# SAM70.net
KiCad netlist of a schematic drawn in Altium Designer
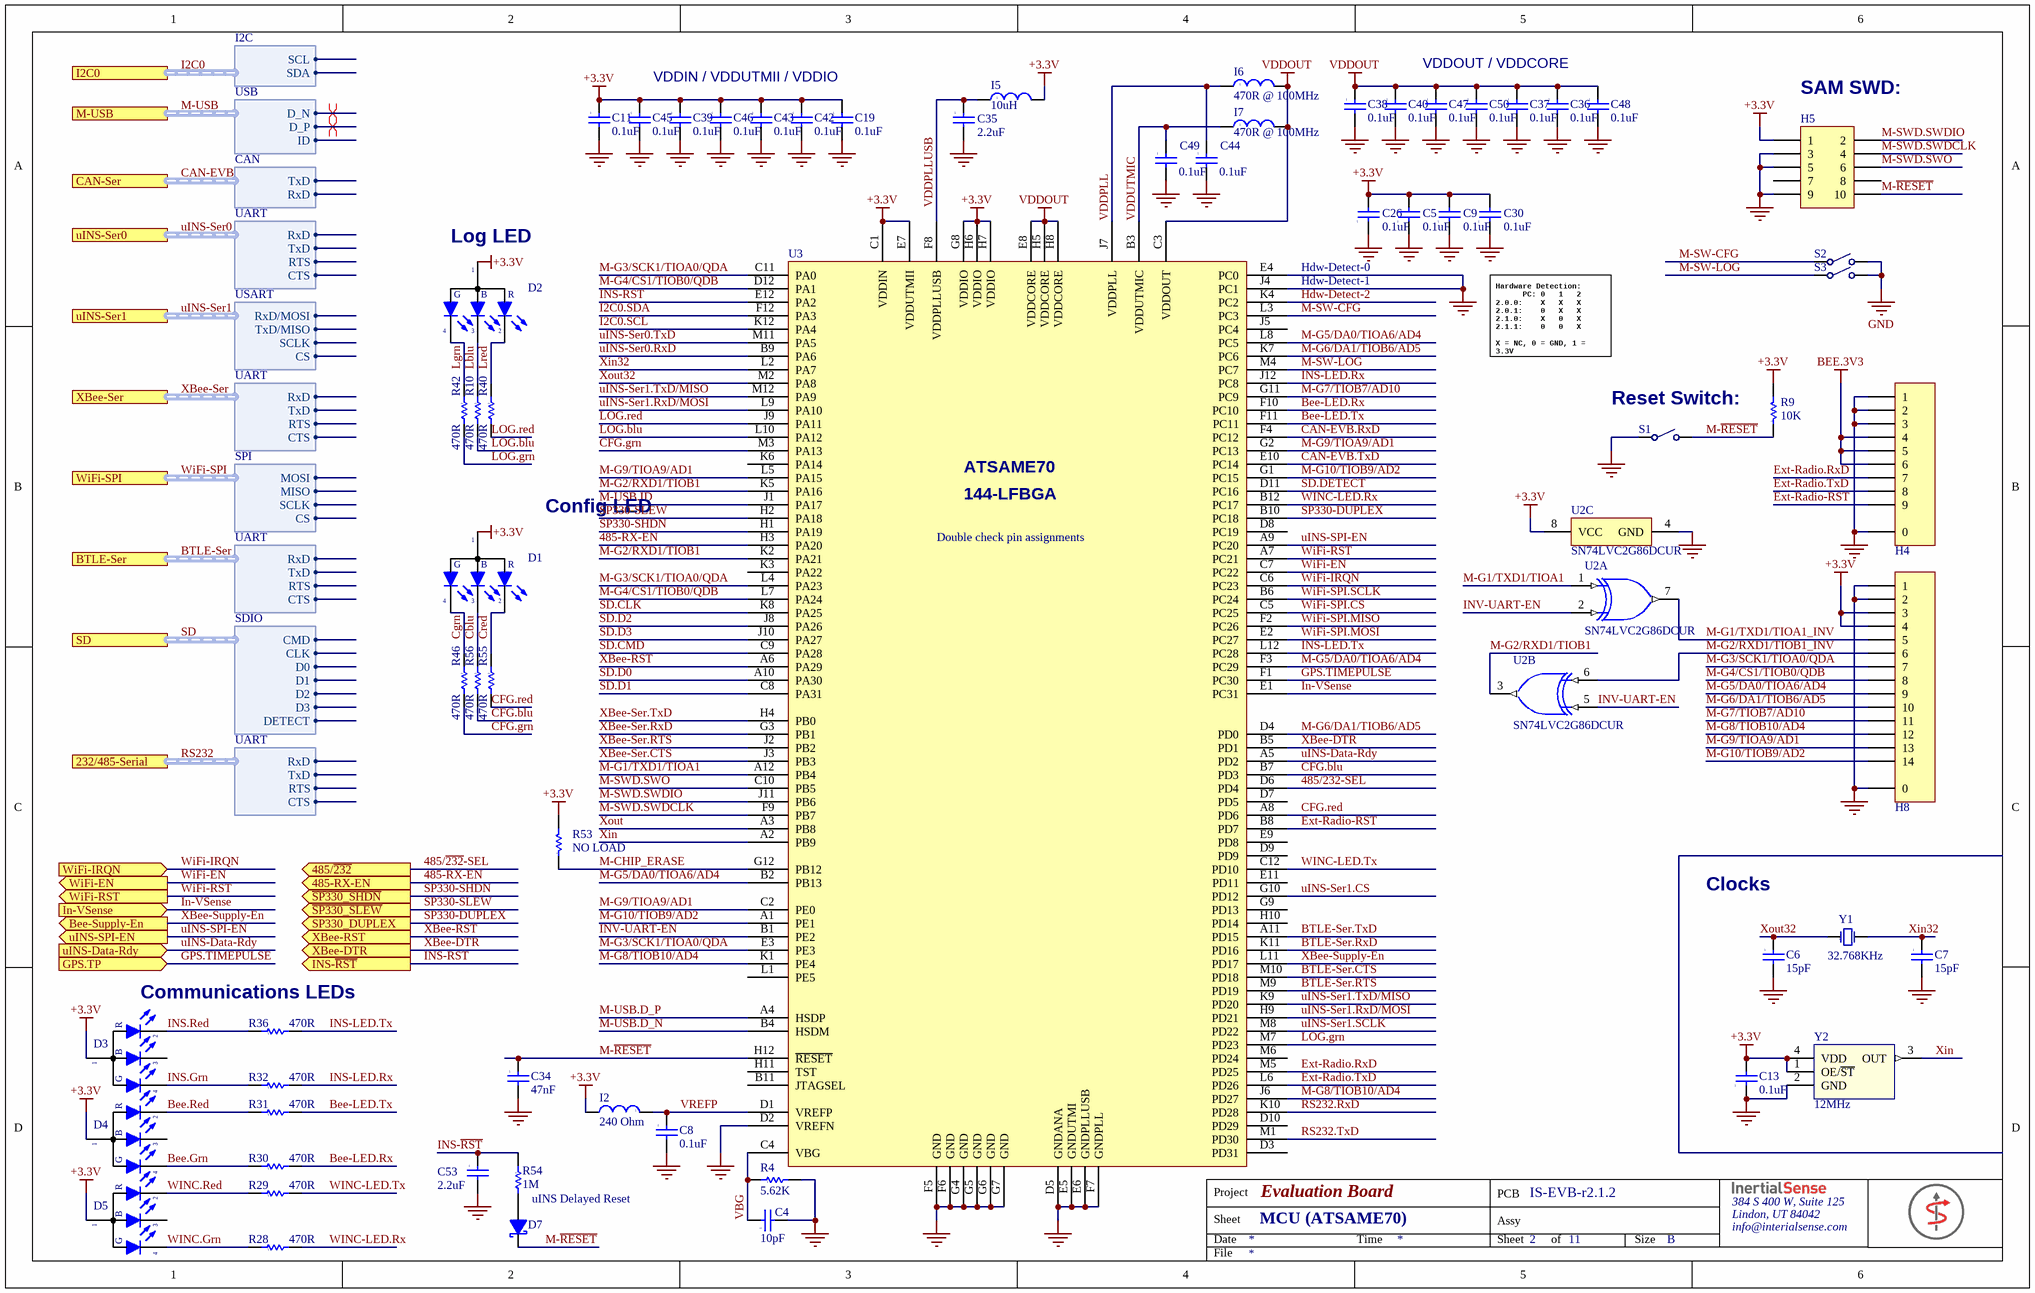
[diagram p0: SAM70.SchDoc]

(export (version "E")
  (design (tool "Eeschema 10.0.6"))
  (components
    (comp (ref "C4")
      (value "10pF")
      (footprint "0402")
      (description "CAP CER 10PF 50V C0G 0402")
      (fields
        (field (name "MANUFACTURER") "TDK")
        (field (name "MANUFACTURER PART NUMBER") "C1005C0G1H100D050BA")
        (field (name "PUBLISHER") "Altium Limited")
      )
      (libsource (lib "General") (part "Cap"))
    )
    (comp (ref "C5")
      (value "0.1uF")
      (footprint "0402")
      (description "CAP CER .10UF 50V X7R 10% 0402")
      (fields
        (field (name "MANUFACTURER") "TDK Corporation")
        (field (name "MANUFACTURER PART NUMBER") "C1005X7R1H104K")
        (field (name "PUBLISHER") "Altium Limited")
      )
      (libsource (lib "") (part "Cap_1"))
    )
    (comp (ref "C6")
      (value "15pF")
      (footprint "0402")
      (description "CAP CER 15PF 16V C0G/NP0 0402")
      (fields
        (field (name "MANUFACTURER") "KEMET")
        (field (name "MANUFACTURER PART NUMBER") "C0402C150J4GACTU")
        (field (name "PUBLISHER") "Altium Limited")
      )
      (libsource (lib "General") (part "Cap"))
    )
    (comp (ref "C7")
      (value "15pF")
      (footprint "0402")
      (description "CAP CER 15PF 16V C0G/NP0 0402")
      (fields
        (field (name "MANUFACTURER") "KEMET")
        (field (name "MANUFACTURER PART NUMBER") "C0402C150J4GACTU")
        (field (name "PUBLISHER") "Altium Limited")
      )
      (libsource (lib "General") (part "Cap"))
    )
    (comp (ref "C8")
      (value "0.1uF")
      (footprint "0201")
      (description "CAP CER 0.1UF 25V X5R 0201")
      (fields
        (field (name "MANUFACTURER") "Murata")
        (field (name "MANUFACTURER PART NUMBER") "GRM033R6YA104KE14D")
        (field (name "PUBLISHER") "Altium Limited")
      )
      (libsource (lib "General") (part "Cap"))
    )
    (comp (ref "C9")
      (value "0.1uF")
      (footprint "0402")
      (description "CAP CER .10UF 50V X7R 10% 0402")
      (fields
        (field (name "MANUFACTURER") "TDK Corporation")
        (field (name "MANUFACTURER PART NUMBER") "C1005X7R1H104K")
        (field (name "PUBLISHER") "Altium Limited")
      )
      (libsource (lib "") (part "Cap_1"))
    )
    (comp (ref "C11")
      (value "0.1uF")
      (footprint "0201")
      (description "CAP CER 0.1UF 25V X5R 0201")
      (fields
        (field (name "MANUFACTURER") "Murata")
        (field (name "MANUFACTURER PART NUMBER") "GRM033R6YA104KE14D")
        (field (name "PUBLISHER") "Altium Limited")
      )
      (libsource (lib "General") (part "Cap"))
    )
    (comp (ref "C13")
      (value "0.1uF")
      (footprint "0402")
      (description "CAP CER .10UF 50V X7R 10% 0402")
      (fields
        (field (name "MANUFACTURER") "TDK Corporation")
        (field (name "MANUFACTURER PART NUMBER") "C1005X7R1H104K")
        (field (name "PUBLISHER") "Altium Limited")
      )
      (libsource (lib "") (part "Cap_1"))
    )
    (comp (ref "C19")
      (value "0.1uF")
      (footprint "0201")
      (description "CAP CER 0.1UF 25V X5R 0201")
      (fields
        (field (name "MANUFACTURER") "Murata")
        (field (name "MANUFACTURER PART NUMBER") "GRM033R6YA104KE14D")
        (field (name "PUBLISHER") "Altium Limited")
      )
      (libsource (lib "General") (part "Cap"))
    )
    (comp (ref "C26")
      (value "0.1uF")
      (footprint "0402")
      (description "CAP CER .10UF 50V X7R 10% 0402")
      (fields
        (field (name "MANUFACTURER") "TDK Corporation")
        (field (name "MANUFACTURER PART NUMBER") "C1005X7R1H104K")
        (field (name "PUBLISHER") "Altium Limited")
      )
      (libsource (lib "") (part "Cap_1"))
    )
    (comp (ref "C30")
      (value "0.1uF")
      (footprint "0402")
      (description "CAP CER .10UF 50V X7R 10% 0402")
      (fields
        (field (name "MANUFACTURER") "TDK Corporation")
        (field (name "MANUFACTURER PART NUMBER") "C1005X7R1H104K")
        (field (name "PUBLISHER") "Altium Limited")
      )
      (libsource (lib "") (part "Cap_1"))
    )
    (comp (ref "C34")
      (value "47nF")
      (footprint "0402")
      (description "CAP CER 0.047UF 16V Y5V 0402")
      (fields
        (field (name "MANUFACTURER") "Yageo")
        (field (name "MANUFACTURER PART NUMBER") "CC0402ZRY5V7BB473")
        (field (name "PUBLISHER") "Altium Limited")
      )
      (libsource (lib "General") (part "Cap"))
    )
    (comp (ref "C35")
      (value "Cap")
      (footprint "0603")
      (description "CAP CER 2.2UF 6.3V X5R 0603")
      (fields
        (field (name "MANUFACTURER") "Samsung")
        (field (name "MANUFACTURER PART NUMBER") "CL10A225KQ8NNWC")
        (field (name "CAPACITANCE") "2.2uF")
      )
      (libsource (lib "General") (part "Cap"))
    )
    (comp (ref "C36")
      (value "0.1uF")
      (footprint "0201")
      (description "CAP CER 0.1UF 25V X5R 0201")
      (fields
        (field (name "MANUFACTURER") "Murata")
        (field (name "MANUFACTURER PART NUMBER") "GRM033R6YA104KE14D")
        (field (name "PUBLISHER") "Altium Limited")
      )
      (libsource (lib "General") (part "Cap"))
    )
    (comp (ref "C37")
      (value "0.1uF")
      (footprint "0201")
      (description "CAP CER 0.1UF 25V X5R 0201")
      (fields
        (field (name "MANUFACTURER") "Murata")
        (field (name "MANUFACTURER PART NUMBER") "GRM033R6YA104KE14D")
        (field (name "PUBLISHER") "Altium Limited")
      )
      (libsource (lib "General") (part "Cap"))
    )
    (comp (ref "C38")
      (value "0.1uF")
      (footprint "0201")
      (description "CAP CER 0.1UF 25V X5R 0201")
      (fields
        (field (name "MANUFACTURER") "Murata")
        (field (name "MANUFACTURER PART NUMBER") "GRM033R6YA104KE14D")
        (field (name "PUBLISHER") "Altium Limited")
      )
      (libsource (lib "General") (part "Cap"))
    )
    (comp (ref "C39")
      (value "0.1uF")
      (footprint "0201")
      (description "CAP CER 0.1UF 25V X5R 0201")
      (fields
        (field (name "MANUFACTURER") "Murata")
        (field (name "MANUFACTURER PART NUMBER") "GRM033R6YA104KE14D")
        (field (name "PUBLISHER") "Altium Limited")
      )
      (libsource (lib "General") (part "Cap"))
    )
    (comp (ref "C40")
      (value "0.1uF")
      (footprint "0201")
      (description "CAP CER 0.1UF 25V X5R 0201")
      (fields
        (field (name "MANUFACTURER") "Murata")
        (field (name "MANUFACTURER PART NUMBER") "GRM033R6YA104KE14D")
        (field (name "PUBLISHER") "Altium Limited")
      )
      (libsource (lib "General") (part "Cap"))
    )
    (comp (ref "C42")
      (value "0.1uF")
      (footprint "0201")
      (description "CAP CER 0.1UF 25V X5R 0201")
      (fields
        (field (name "MANUFACTURER") "Murata")
        (field (name "MANUFACTURER PART NUMBER") "GRM033R6YA104KE14D")
        (field (name "PUBLISHER") "Altium Limited")
      )
      (libsource (lib "General") (part "Cap"))
    )
    (comp (ref "C43")
      (value "0.1uF")
      (footprint "0201")
      (description "CAP CER 0.1UF 25V X5R 0201")
      (fields
        (field (name "MANUFACTURER") "Murata")
        (field (name "MANUFACTURER PART NUMBER") "GRM033R6YA104KE14D")
        (field (name "PUBLISHER") "Altium Limited")
      )
      (libsource (lib "General") (part "Cap"))
    )
    (comp (ref "C44")
      (value "0.1uF")
      (footprint "0201")
      (description "CAP CER 0.1UF 25V X5R 0201")
      (fields
        (field (name "MANUFACTURER") "Murata")
        (field (name "MANUFACTURER PART NUMBER") "GRM033R6YA104KE14D")
        (field (name "PUBLISHER") "Altium Limited")
      )
      (libsource (lib "General") (part "Cap"))
    )
    (comp (ref "C45")
      (value "0.1uF")
      (footprint "0201")
      (description "CAP CER 0.1UF 25V X5R 0201")
      (fields
        (field (name "MANUFACTURER") "Murata")
        (field (name "MANUFACTURER PART NUMBER") "GRM033R6YA104KE14D")
        (field (name "PUBLISHER") "Altium Limited")
      )
      (libsource (lib "General") (part "Cap"))
    )
    (comp (ref "C46")
      (value "0.1uF")
      (footprint "0201")
      (description "CAP CER 0.1UF 25V X5R 0201")
      (fields
        (field (name "MANUFACTURER") "Murata")
        (field (name "MANUFACTURER PART NUMBER") "GRM033R6YA104KE14D")
        (field (name "PUBLISHER") "Altium Limited")
      )
      (libsource (lib "General") (part "Cap"))
    )
    (comp (ref "C47")
      (value "0.1uF")
      (footprint "0201")
      (description "CAP CER 0.1UF 25V X5R 0201")
      (fields
        (field (name "MANUFACTURER") "Murata")
        (field (name "MANUFACTURER PART NUMBER") "GRM033R6YA104KE14D")
        (field (name "PUBLISHER") "Altium Limited")
      )
      (libsource (lib "General") (part "Cap"))
    )
    (comp (ref "C48")
      (value "0.1uF")
      (footprint "0201")
      (description "CAP CER 0.1UF 25V X5R 0201")
      (fields
        (field (name "MANUFACTURER") "Murata")
        (field (name "MANUFACTURER PART NUMBER") "GRM033R6YA104KE14D")
        (field (name "PUBLISHER") "Altium Limited")
      )
      (libsource (lib "General") (part "Cap"))
    )
    (comp (ref "C49")
      (value "0.1uF")
      (footprint "0201")
      (description "CAP CER 0.1UF 25V X5R 0201")
      (fields
        (field (name "MANUFACTURER") "Murata")
        (field (name "MANUFACTURER PART NUMBER") "GRM033R6YA104KE14D")
        (field (name "PUBLISHER") "Altium Limited")
      )
      (libsource (lib "General") (part "Cap"))
    )
    (comp (ref "C50")
      (value "0.1uF")
      (footprint "0201")
      (description "CAP CER 0.1UF 25V X5R 0201")
      (fields
        (field (name "MANUFACTURER") "Murata")
        (field (name "MANUFACTURER PART NUMBER") "GRM033R6YA104KE14D")
        (field (name "PUBLISHER") "Altium Limited")
      )
      (libsource (lib "General") (part "Cap"))
    )
    (comp (ref "C53")
      (value "Cap")
      (footprint "0603")
      (description "CAP CER 2.2UF 6.3V X5R 0603")
      (fields
        (field (name "MANUFACTURER") "Samsung")
        (field (name "MANUFACTURER PART NUMBER") "CL10A225KQ8NNWC")
        (field (name "CAPACITANCE") "2.2uF")
      )
      (libsource (lib "General") (part "Cap"))
    )
    (comp (ref "D1")
      (value "LED-RGB")
      (footprint "LED0404")
      (description "LED RGB DIFFUSED 0404 SMD")
      (fields
        (field (name "MANUFACTURER") "Rohm Semiconductor")
        (field (name "MANUFACTURER PART NUMBER") "SMLP34RGB2W3")
        (field (name "PUBLISHER") "Altium Limited")
      )
      (libsource (lib "General") (part "LED-RGB"))
    )
    (comp (ref "D2")
      (value "LED-RGB")
      (footprint "LED0404")
      (description "LED RGB DIFFUSED 0404 SMD")
      (fields
        (field (name "MANUFACTURER") "Rohm Semiconductor")
        (field (name "MANUFACTURER PART NUMBER") "SMLP34RGB2W3")
        (field (name "PUBLISHER") "Altium Limited")
      )
      (libsource (lib "General") (part "LED-RGB"))
    )
    (comp (ref "D3")
      (value "LED-RGB")
      (footprint "LED0404")
      (description "LED RGB DIFFUSED 0404 SMD")
      (fields
        (field (name "MANUFACTURER") "Rohm Semiconductor")
        (field (name "MANUFACTURER PART NUMBER") "SMLP34RGB2W3")
        (field (name "PUBLISHER") "Altium Limited")
      )
      (libsource (lib "General") (part "LED-RGB"))
    )
    (comp (ref "D4")
      (value "LED-RGB")
      (footprint "LED0404")
      (description "LED RGB DIFFUSED 0404 SMD")
      (fields
        (field (name "MANUFACTURER") "Rohm Semiconductor")
        (field (name "MANUFACTURER PART NUMBER") "SMLP34RGB2W3")
        (field (name "PUBLISHER") "Altium Limited")
      )
      (libsource (lib "General") (part "LED-RGB"))
    )
    (comp (ref "D5")
      (value "LED-RGB")
      (footprint "LED0404")
      (description "LED RGB DIFFUSED 0404 SMD")
      (fields
        (field (name "MANUFACTURER") "Rohm Semiconductor")
        (field (name "MANUFACTURER PART NUMBER") "SMLP34RGB2W3")
        (field (name "PUBLISHER") "Altium Limited")
      )
      (libsource (lib "General") (part "LED-RGB"))
    )
    (comp (ref "D7")
      (value "Diode - Schottky")
      (footprint "D0603B")
      (description "DIODE SCHOTTKY 30V 2A 0603")
      (fields
        (field (name "MANUFACTURER") "Vishay")
        (field (name "MANUFACTURER PART NUMBER") "VSKY20301608-G4-08")
      )
      (libsource (lib "General") (part "Diode - Schottky"))
    )
    (comp (ref "H4")
      (value "Hdr - 9pin - mount")
      (footprint "SM09B-GHS-TB(LF)(SN)")
      (description "CONN HEADER GH SIDE 9POS 1.25MM")
      (fields
        (field (name "MANUFACTURER") "JST")
        (field (name "MANUFACTURER PART NUMBER") "SM09B-GHS-TB(LF)(SN)")
      )
      (libsource (lib "Connectors") (part "Hdr - 9pin - mount"))
    )
    (comp (ref "H5")
      (value "Hdr - 5x2pin")
      (footprint "FTSH-105-01-L-DV-K-A-P")
      (description "CONN HEADER 10POS DUAL .05\" SMD")
      (fields
        (field (name "MANUFACTURER") "Samtec")
        (field (name "MANUFACTURER PART NUMBER") "FTSH-105-01-L-DV-K-A-P")
      )
      (libsource (lib "Connectors") (part "Hdr - 5x2pin"))
    )
    (comp (ref "H8")
      (value "Hdr - 14pin - mount")
      (footprint "SM14B-GHS-TB(LF)(SN)")
      (description "CONN HEADER GH SIDE 14POS 1.25MM")
      (fields
        (field (name "MANUFACTURER") "JST")
        (field (name "MANUFACTURER PART NUMBER") "SM14B-GHS-TB(LF)(SN)")
      )
      (libsource (lib "Connectors") (part "Hdr - 14pin - mount"))
    )
    (comp (ref "I2")
      (value "240 Ohm")
      (footprint "0201")
      (description "FERRITE BEAD 240 OHM 0201 1LN")
      (fields
        (field (name "MANUFACTURER") "TDK Corporation")
        (field (name "MANUFACTURER PART NUMBER") "MMZ0603S241HT000")
      )
      (libsource (lib "") (part "Inductor_1"))
    )
    (comp (ref "I5")
      (value "Inductor")
      (footprint "0806")
      (description "FIXED IND 10UH 350MA 1.066 OHM")
      (fields
        (field (name "MANUFACTURER") "Taiyo Yuden")
        (field (name "MANUFACTURER PART NUMBER") "CBC2016T100M")
        (field (name "INDUCTANCE") "10uH")
      )
      (libsource (lib "General") (part "Inductor"))
    )
    (comp (ref "I6")
      (value "470R @ 100MHz")
      (footprint "0402")
      (description "FERRITE BEAD 470 OHM 0402")
      (fields
        (field (name "MANUFACTURER") "Taiyo Yuden")
        (field (name "MANUFACTURER PART NUMBER") "BK1005HM471-T")
      )
      (libsource (lib "General") (part "Inductor"))
    )
    (comp (ref "I7")
      (value "470R @ 100MHz")
      (footprint "0402")
      (description "FERRITE BEAD 470 OHM 0402")
      (fields
        (field (name "MANUFACTURER") "Taiyo Yuden")
        (field (name "MANUFACTURER PART NUMBER") "BK1005HM471-T")
      )
      (libsource (lib "General") (part "Inductor"))
    )
    (comp (ref "R4")
      (value "5.62K")
      (footprint "R0402")
      (description "RES SMD 5.62K OHM 1% 1/10W 0402")
      (fields
        (field (name "MANUFACTURER") "Panasonic")
        (field (name "MANUFACTURER PART NUMBER") "ERJ-2RKF5621X")
      )
      (libsource (lib "") (part "Res_1"))
    )
    (comp (ref "R9")
      (value "10K")
      (footprint "R0402")
      (description "RES 10K OHM 1/16W 1% 0402 SMD")
      (fields
        (field (name "MANUFACTURER") "Panasonic")
        (field (name "MANUFACTURER PART NUMBER") "ERJ-2RKF1002X")
      )
      (libsource (lib "General") (part "Res"))
    )
    (comp (ref "R10")
      (value "470R")
      (footprint "R0402")
      (description "RES SMD 470 OHM 5% 1/16W 0402")
      (fields
        (field (name "MANUFACTURER") "Vishay Dale")
        (field (name "MANUFACTURER PART NUMBER") "CRCW0402470RJNED")
      )
      (libsource (lib "") (part "Res_1"))
    )
    (comp (ref "R28")
      (value "470R")
      (footprint "R0402")
      (description "RES SMD 470 OHM 5% 1/16W 0402")
      (fields
        (field (name "MANUFACTURER") "Vishay Dale")
        (field (name "MANUFACTURER PART NUMBER") "CRCW0402470RJNED")
      )
      (libsource (lib "") (part "Res_1"))
    )
    (comp (ref "R29")
      (value "470R")
      (footprint "R0402")
      (description "RES SMD 470 OHM 5% 1/16W 0402")
      (fields
        (field (name "MANUFACTURER") "Vishay Dale")
        (field (name "MANUFACTURER PART NUMBER") "CRCW0402470RJNED")
      )
      (libsource (lib "") (part "Res_1"))
    )
    (comp (ref "R30")
      (value "470R")
      (footprint "R0402")
      (description "RES SMD 470 OHM 5% 1/16W 0402")
      (fields
        (field (name "MANUFACTURER") "Vishay Dale")
        (field (name "MANUFACTURER PART NUMBER") "CRCW0402470RJNED")
      )
      (libsource (lib "") (part "Res_1"))
    )
    (comp (ref "R31")
      (value "470R")
      (footprint "R0402")
      (description "RES SMD 470 OHM 5% 1/16W 0402")
      (fields
        (field (name "MANUFACTURER") "Vishay Dale")
        (field (name "MANUFACTURER PART NUMBER") "CRCW0402470RJNED")
      )
      (libsource (lib "") (part "Res_1"))
    )
    (comp (ref "R32")
      (value "470R")
      (footprint "R0402")
      (description "RES SMD 470 OHM 5% 1/16W 0402")
      (fields
        (field (name "MANUFACTURER") "Vishay Dale")
        (field (name "MANUFACTURER PART NUMBER") "CRCW0402470RJNED")
      )
      (libsource (lib "") (part "Res_1"))
    )
    (comp (ref "R36")
      (value "470R")
      (footprint "R0402")
      (description "RES SMD 470 OHM 5% 1/16W 0402")
      (fields
        (field (name "MANUFACTURER") "Vishay Dale")
        (field (name "MANUFACTURER PART NUMBER") "CRCW0402470RJNED")
      )
      (libsource (lib "") (part "Res_1"))
    )
    (comp (ref "R40")
      (value "470R")
      (footprint "R0402")
      (description "RES SMD 470 OHM 5% 1/16W 0402")
      (fields
        (field (name "MANUFACTURER") "Vishay Dale")
        (field (name "MANUFACTURER PART NUMBER") "CRCW0402470RJNED")
      )
      (libsource (lib "") (part "Res_1"))
    )
    (comp (ref "R42")
      (value "470R")
      (footprint "R0402")
      (description "RES SMD 470 OHM 5% 1/16W 0402")
      (fields
        (field (name "MANUFACTURER") "Vishay Dale")
        (field (name "MANUFACTURER PART NUMBER") "CRCW0402470RJNED")
      )
      (libsource (lib "") (part "Res_1"))
    )
    (comp (ref "R46")
      (value "470R")
      (footprint "R0402")
      (description "RES SMD 470 OHM 5% 1/16W 0402")
      (fields
        (field (name "MANUFACTURER") "Vishay Dale")
        (field (name "MANUFACTURER PART NUMBER") "CRCW0402470RJNED")
      )
      (libsource (lib "") (part "Res_1"))
    )
    (comp (ref "R53")
      (value "NO LOAD")
      (footprint "R0402")
      (description "RES 1.00K OHM 1/16W 1% 0402 SMD")
      (fields (field (name "Comment") "Res"))
      (libsource (lib "General") (part "Res"))
    )
    (comp (ref "R54")
      (value "1M")
      (footprint "R0402")
      (description "RES SMD 1M OHM 1% 1/16W 0402")
      (fields
        (field (name "MANUFACTURER") "Yageo")
        (field (name "MANUFACTURER PART NUMBER") "RC0402FR-071ML")
      )
      (libsource (lib "") (part "Res_1"))
    )
    (comp (ref "R55")
      (value "470R")
      (footprint "R0402")
      (description "RES SMD 470 OHM 5% 1/16W 0402")
      (fields
        (field (name "MANUFACTURER") "Vishay Dale")
        (field (name "MANUFACTURER PART NUMBER") "CRCW0402470RJNED")
      )
      (libsource (lib "") (part "Res_1"))
    )
    (comp (ref "R56")
      (value "470R")
      (footprint "R0402")
      (description "RES SMD 470 OHM 5% 1/16W 0402")
      (fields
        (field (name "MANUFACTURER") "Vishay Dale")
        (field (name "MANUFACTURER PART NUMBER") "CRCW0402470RJNED")
      )
      (libsource (lib "") (part "Res_1"))
    )
    (comp (ref "S1")
      (value "SPST Switch")
      (footprint "PTS810")
      (description "SWITCH TACTILE SPST-NO 0.05A 16V")
      (fields
        (field (name "MANUFACTURER") "ITT C&K")
        (field (name "MANUFACTURER PART NUMBER") "PTS810SJK250SMTRLFS")
      )
      (libsource (lib "General") (part "Switch SPST"))
    )
    (comp (ref "S2")
      (value "SPST Switch")
      (footprint "PTS810")
      (description "SWITCH TACTILE SPST-NO 0.05A 16V")
      (fields
        (field (name "MANUFACTURER") "ITT C&K")
        (field (name "MANUFACTURER PART NUMBER") "PTS810SJK250SMTRLFS")
      )
      (libsource (lib "General") (part "Switch SPST"))
    )
    (comp (ref "S3")
      (value "SPST Switch")
      (footprint "PTS810")
      (description "SWITCH TACTILE SPST-NO 0.05A 16V")
      (fields
        (field (name "MANUFACTURER") "ITT C&K")
        (field (name "MANUFACTURER PART NUMBER") "PTS810SJK250SMTRLFS")
      )
      (libsource (lib "General") (part "Switch SPST"))
    )
    (comp (ref "U2")
      (value "SN74LVC2G86DCUR")
      (footprint "DCU0008A_N")
      (description "IC GATE XOR 2CH 2-INP US8")
      (fields
        (field (name "GENERIC PART NUMBER") "SN74LVC2G86")
        (field (name "MANUFACTURER") "Texas Instruments")
      )
      (libsource (lib "") (part "SN74LVC2G86DCUR_1"))
    )
    (comp (ref "U3")
      (value "ATSAME70-144")
      (footprint "BGA144C80P12X12_1000X1000X140")
      (description "IC MCU 32BIT 1MB FLASH 144LFBGA")
      (fields
        (field (name "MANUFACTURER") "Microchip")
        (field (name "MANUFACTURER PART NUMBER") "ATSAME70Q20B-CNT")
      )
      (libsource (lib "ICs") (part "ATSAME70-144"))
    )
    (comp (ref "Y1")
      (value "32.768KHz")
      (footprint "CRYMP2012X06L")
      (description "CRYSTAL 32.7680KHZ 9PF SMD")
      (fields
        (field (name "MANUFACTURER") "Abracon LLC")
        (field (name "MANUFACTURER PART NUMBER") "ABS06-32.768KHZ-9-1-T")
      )
      (libsource (lib "General") (part "Crystal"))
    )
    (comp (ref "Y2")
      (value "12MHz")
      (footprint "ABM10_2.5_x_2.0")
      (description "OSC XO 12.000MHZ HCMOS SMD")
      (fields
        (field (name "MANUFACTURER") "ECS Inc.")
        (field (name "MANUFACTURER PART NUMBER") "ECS-2520S33-120-FN-TR")
      )
      (libsource (lib "General") (part "Oscillator2"))
    )
  )
  (nets
    (net (code "11") (name "+3.3V") (class "Default")
      (node (ref "C11") (pin "1") (pinfunction "1_1") (pintype "passive"))
      (node (ref "C13") (pin "2") (pinfunction "2_2") (pintype "passive"))
      (node (ref "C19") (pin "1") (pinfunction "1_1") (pintype "passive"))
      (node (ref "C26") (pin "2") (pinfunction "2_2") (pintype "passive"))
      (node (ref "C30") (pin "2") (pinfunction "2_2") (pintype "passive"))
      (node (ref "C39") (pin "1") (pinfunction "1_1") (pintype "passive"))
      (node (ref "C42") (pin "1") (pinfunction "1_1") (pintype "passive"))
      (node (ref "C43") (pin "1") (pinfunction "1_1") (pintype "passive"))
      (node (ref "C45") (pin "1") (pinfunction "1_1") (pintype "passive"))
      (node (ref "C46") (pin "1") (pinfunction "1_1") (pintype "passive"))
      (node (ref "C5") (pin "2") (pinfunction "2_2") (pintype "passive"))
      (node (ref "C9") (pin "2") (pinfunction "2_2") (pintype "passive"))
      (node (ref "D1") (pin "1") (pinfunction "1_1") (pintype "passive"))
      (node (ref "D2") (pin "1") (pinfunction "1_1") (pintype "passive"))
      (node (ref "D3") (pin "1") (pinfunction "1_1") (pintype "passive"))
      (node (ref "D4") (pin "1") (pinfunction "1_1") (pintype "passive"))
      (node (ref "D5") (pin "1") (pinfunction "1_1") (pintype "passive"))
      (node (ref "H5") (pin "1") (pinfunction "1_1") (pintype "passive"))
      (node (ref "H8") (pin "3") (pinfunction "3_3") (pintype "passive"))
      (node (ref "H8") (pin "4") (pinfunction "4_4") (pintype "passive"))
      (node (ref "I2") (pin "2") (pinfunction "2_2") (pintype "passive"))
      (node (ref "I5") (pin "2") (pinfunction "2_2") (pintype "passive"))
      (node (ref "R53") (pin "2") (pinfunction "2_2") (pintype "passive"))
      (node (ref "R9") (pin "2") (pinfunction "2_2") (pintype "passive"))
      (node (ref "U2") (pin "8") (pinfunction "VCC_8") (pintype "power_in"))
      (node (ref "U3") (pin "C1") (pinfunction "VDDIN_C1") (pintype "passive"))
      (node (ref "U3") (pin "E7") (pinfunction "VDDUTMII_E7") (pintype "passive"))
      (node (ref "U3") (pin "G8") (pinfunction "VDDIO_G8") (pintype "passive"))
      (node (ref "U3") (pin "H6") (pinfunction "VDDIO_H6") (pintype "passive"))
      (node (ref "U3") (pin "H7") (pinfunction "VDDIO_H7") (pintype "passive"))
      (node (ref "Y2") (pin "1") (pinfunction "OE/~{ST}_1") (pintype "passive"))
      (node (ref "Y2") (pin "4") (pinfunction "VDD_4") (pintype "passive"))
    )
    (net (code "12") (name "/485-RX-EN") (class "Default")
      (node (ref "U3") (pin "H3") (pinfunction "PA20_H3") (pintype "passive"))
    )
    (net (code "13") (name "/485{slash}~{232}-SEL") (class "Default")
      (node (ref "U3") (pin "D6") (pinfunction "PD4_D6") (pintype "passive"))
    )
    (net (code "14") (name "/BTLE-Ser.CTS") (class "Default")
      (node (ref "U3") (pin "M10") (pinfunction "PD18_M10") (pintype "passive"))
    )
    (net (code "15") (name "/BTLE-Ser.RTS") (class "Default")
      (node (ref "U3") (pin "M9") (pinfunction "PD19_M9") (pintype "passive"))
    )
    (net (code "16") (name "/BTLE-Ser.RxD") (class "Default")
      (node (ref "U3") (pin "K11") (pinfunction "PD16_K11") (pintype "passive"))
    )
    (net (code "17") (name "/BTLE-Ser.TxD") (class "Default")
      (node (ref "U3") (pin "A11") (pinfunction "PD15_A11") (pintype "passive"))
    )
    (net (code "19") (name "/Bee-LED.Rx") (class "Default")
      (node (ref "R30") (pin "2") (pinfunction "2_2") (pintype "passive"))
      (node (ref "U3") (pin "F10") (pinfunction "PC10_F10") (pintype "passive"))
    )
    (net (code "20") (name "/Bee-LED.Tx") (class "Default")
      (node (ref "R31") (pin "2") (pinfunction "2_2") (pintype "passive"))
      (node (ref "U3") (pin "F11") (pinfunction "PC11_F11") (pintype "passive"))
    )
    (net (code "21") (name "/Bee.Grn") (class "Default")
      (node (ref "D4") (pin "4") (pinfunction "4_4") (pintype "passive"))
      (node (ref "R30") (pin "1") (pinfunction "1_1") (pintype "passive"))
    )
    (net (code "22") (name "/Bee.Red") (class "Default")
      (node (ref "D4") (pin "2") (pinfunction "2_2") (pintype "passive"))
      (node (ref "R31") (pin "1") (pinfunction "1_1") (pintype "passive"))
    )
    (net (code "23") (name "/CAN-EVB.RxD") (class "Default")
      (node (ref "U3") (pin "F4") (pinfunction "PC12_F4") (pintype "passive"))
    )
    (net (code "24") (name "/CAN-EVB.TxD") (class "Default")
      (node (ref "U3") (pin "E10") (pinfunction "PC14_E10") (pintype "passive"))
    )
    (net (code "26") (name "/CFG.blu") (class "Default")
      (node (ref "R56") (pin "2") (pinfunction "2_2") (pintype "passive"))
      (node (ref "U3") (pin "B7") (pinfunction "PD3_B7") (pintype "passive"))
    )
    (net (code "27") (name "/CFG.grn") (class "Default")
      (node (ref "R46") (pin "2") (pinfunction "2_2") (pintype "passive"))
      (node (ref "U3") (pin "M3") (pinfunction "PA13_M3") (pintype "passive"))
    )
    (net (code "28") (name "/CFG.red") (class "Default")
      (node (ref "R55") (pin "2") (pinfunction "2_2") (pintype "passive"))
      (node (ref "U3") (pin "A8") (pinfunction "PD6_A8") (pintype "passive"))
    )
    (net (code "29") (name "/Cblu") (class "Default")
      (node (ref "D1") (pin "3") (pinfunction "3_3") (pintype "passive"))
      (node (ref "R56") (pin "1") (pinfunction "1_1") (pintype "passive"))
    )
    (net (code "30") (name "/Cgrn") (class "Default")
      (node (ref "D1") (pin "4") (pinfunction "4_4") (pintype "passive"))
      (node (ref "R46") (pin "1") (pinfunction "1_1") (pintype "passive"))
    )
    (net (code "31") (name "/Cred") (class "Default")
      (node (ref "D1") (pin "2") (pinfunction "2_2") (pintype "passive"))
      (node (ref "R55") (pin "1") (pinfunction "1_1") (pintype "passive"))
    )
    (net (code "32") (name "/Ext-Radio-RST") (class "Default")
      (node (ref "H4") (pin "9") (pinfunction "9_9") (pintype "passive"))
      (node (ref "U3") (pin "B8") (pinfunction "PD7_B8") (pintype "passive"))
    )
    (net (code "33") (name "/Ext-Radio.RxD") (class "Default")
      (node (ref "H4") (pin "7") (pinfunction "7_7") (pintype "passive"))
      (node (ref "U3") (pin "M5") (pinfunction "PD25_M5") (pintype "passive"))
    )
    (net (code "34") (name "/Ext-Radio.TxD") (class "Default")
      (node (ref "H4") (pin "8") (pinfunction "8_8") (pintype "passive"))
      (node (ref "U3") (pin "L6") (pinfunction "PD26_L6") (pintype "passive"))
    )
    (net (code "35") (name "/GPS.TIMEPULSE") (class "Default")
      (node (ref "U3") (pin "F1") (pinfunction "PC30_F1") (pintype "passive"))
    )
    (net (code "36") (name "/Hdw-Detect-2") (class "Default")
      (node (ref "U3") (pin "K4") (pinfunction "PC2_K4") (pintype "passive"))
    )
    (net (code "37") (name "/I2C0.SCL") (class "Default")
      (node (ref "U3") (pin "K12") (pinfunction "PA4_K12") (pintype "passive"))
    )
    (net (code "38") (name "/I2C0.SDA") (class "Default")
      (node (ref "U3") (pin "F12") (pinfunction "PA3_F12") (pintype "passive"))
    )
    (net (code "40") (name "/INS-LED.Rx") (class "Default")
      (node (ref "R32") (pin "2") (pinfunction "2_2") (pintype "passive"))
      (node (ref "U3") (pin "J12") (pinfunction "PC8_J12") (pintype "passive"))
    )
    (net (code "41") (name "/INS-LED.Tx") (class "Default")
      (node (ref "R36") (pin "2") (pinfunction "2_2") (pintype "passive"))
      (node (ref "U3") (pin "L12") (pinfunction "PC28_L12") (pintype "passive"))
    )
    (net (code "42") (name "/INS-~{RST}") (class "Default")
      (node (ref "C53") (pin "1") (pinfunction "1_1") (pintype "passive"))
      (node (ref "R54") (pin "1") (pinfunction "1_1") (pintype "passive"))
      (node (ref "U3") (pin "E12") (pinfunction "PA2_E12") (pintype "passive"))
    )
    (net (code "43") (name "/INS.Grn") (class "Default")
      (node (ref "D3") (pin "4") (pinfunction "4_4") (pintype "passive"))
      (node (ref "R32") (pin "1") (pinfunction "1_1") (pintype "passive"))
    )
    (net (code "44") (name "/INS.Red") (class "Default")
      (node (ref "D3") (pin "2") (pinfunction "2_2") (pintype "passive"))
      (node (ref "R36") (pin "1") (pinfunction "1_1") (pintype "passive"))
    )
    (net (code "45") (name "/INV-UART-EN") (class "Default")
      (node (ref "U2") (pin "2") (pinfunction "1B_2") (pintype "input"))
      (node (ref "U2") (pin "5") (pinfunction "2A_5") (pintype "input"))
      (node (ref "U3") (pin "B1") (pinfunction "PE2_B1") (pintype "passive"))
    )
    (net (code "46") (name "/In-VSense") (class "Default")
      (node (ref "U3") (pin "E1") (pinfunction "PC31_E1") (pintype "passive"))
    )
    (net (code "47") (name "/LOG.blu") (class "Default")
      (node (ref "R10") (pin "2") (pinfunction "2_2") (pintype "passive"))
      (node (ref "U3") (pin "L10") (pinfunction "PA12_L10") (pintype "passive"))
    )
    (net (code "48") (name "/LOG.grn") (class "Default")
      (node (ref "R42") (pin "2") (pinfunction "2_2") (pintype "passive"))
      (node (ref "U3") (pin "M7") (pinfunction "PD23_M7") (pintype "passive"))
    )
    (net (code "49") (name "/LOG.red") (class "Default")
      (node (ref "R40") (pin "2") (pinfunction "2_2") (pintype "passive"))
      (node (ref "U3") (pin "J9") (pinfunction "PA11_J9") (pintype "passive"))
    )
    (net (code "50") (name "/Lblu") (class "Default")
      (node (ref "D2") (pin "3") (pinfunction "3_3") (pintype "passive"))
      (node (ref "R10") (pin "1") (pinfunction "1_1") (pintype "passive"))
    )
    (net (code "51") (name "/Lgrn") (class "Default")
      (node (ref "D2") (pin "4") (pinfunction "4_4") (pintype "passive"))
      (node (ref "R42") (pin "1") (pinfunction "1_1") (pintype "passive"))
    )
    (net (code "52") (name "/Lred") (class "Default")
      (node (ref "D2") (pin "2") (pinfunction "2_2") (pintype "passive"))
      (node (ref "R40") (pin "1") (pinfunction "1_1") (pintype "passive"))
    )
    (net (code "53") (name "/M-CHIP_ERASE") (class "Default")
      (node (ref "R53") (pin "1") (pinfunction "1_1") (pintype "passive"))
      (node (ref "U3") (pin "G12") (pinfunction "PB12_G12") (pintype "passive"))
    )
    (net (code "54") (name "/M-G1{slash}TXD1{slash}TIOA1") (class "Default")
      (node (ref "U2") (pin "1") (pinfunction "1A_1") (pintype "input"))
      (node (ref "U3") (pin "A12") (pinfunction "PB4_A12") (pintype "passive"))
    )
    (net (code "55") (name "/M-G1{slash}TXD1{slash}TIOA1_INV") (class "Default")
      (node (ref "H8") (pin "5") (pinfunction "5_5") (pintype "passive"))
      (node (ref "U2") (pin "7") (pinfunction "1Y_7") (pintype "output"))
    )
    (net (code "56") (name "/M-G2{slash}RXD1{slash}TIOB1") (class "Default")
      (node (ref "U2") (pin "3") (pinfunction "2Y_3") (pintype "output"))
      (node (ref "U3") (pin "K2") (pinfunction "PA21_K2") (pintype "passive"))
      (node (ref "U3") (pin "K5") (pinfunction "PA16_K5") (pintype "passive"))
    )
    (net (code "57") (name "/M-G2{slash}RXD1{slash}TIOB1_INV") (class "Default")
      (node (ref "H8") (pin "6") (pinfunction "6_6") (pintype "passive"))
      (node (ref "U2") (pin "6") (pinfunction "2B_6") (pintype "input"))
    )
    (net (code "58") (name "/M-G3{slash}SCK1{slash}TIOA0{slash}QDA") (class "Default")
      (node (ref "H8") (pin "7") (pinfunction "7_7") (pintype "passive"))
      (node (ref "U3") (pin "C11") (pinfunction "PA0_C11") (pintype "passive"))
      (node (ref "U3") (pin "E3") (pinfunction "PE3_E3") (pintype "passive"))
      (node (ref "U3") (pin "L4") (pinfunction "PA23_L4") (pintype "passive"))
    )
    (net (code "59") (name "/M-G4{slash}CS1{slash}TIOB0{slash}QDB") (class "Default")
      (node (ref "H8") (pin "8") (pinfunction "8_8") (pintype "passive"))
      (node (ref "U3") (pin "D12") (pinfunction "PA1_D12") (pintype "passive"))
      (node (ref "U3") (pin "L7") (pinfunction "PA24_L7") (pintype "passive"))
    )
    (net (code "60") (name "/M-G5{slash}DA0{slash}TIOA6{slash}AD4") (class "Default")
      (node (ref "H8") (pin "9") (pinfunction "9_9") (pintype "passive"))
      (node (ref "U3") (pin "B2") (pinfunction "PB13_B2") (pintype "passive"))
      (node (ref "U3") (pin "F3") (pinfunction "PC29_F3") (pintype "passive"))
      (node (ref "U3") (pin "L8") (pinfunction "PC5_L8") (pintype "passive"))
    )
    (net (code "61") (name "/M-G6{slash}DA1{slash}TIOB6{slash}AD5") (class "Default")
      (node (ref "H8") (pin "10") (pinfunction "10_10") (pintype "passive"))
      (node (ref "U3") (pin "D4") (pinfunction "PD0_D4") (pintype "passive"))
      (node (ref "U3") (pin "K7") (pinfunction "PC6_K7") (pintype "passive"))
    )
    (net (code "62") (name "/M-G7{slash}TIOB7{slash}AD10") (class "Default")
      (node (ref "H8") (pin "11") (pinfunction "11_11") (pintype "passive"))
      (node (ref "U3") (pin "G11") (pinfunction "PC9_G11") (pintype "passive"))
    )
    (net (code "63") (name "/M-G8{slash}TIOB10{slash}AD4") (class "Default")
      (node (ref "H8") (pin "12") (pinfunction "12_12") (pintype "passive"))
      (node (ref "U3") (pin "J6") (pinfunction "PD27_J6") (pintype "passive"))
      (node (ref "U3") (pin "K1") (pinfunction "PE4_K1") (pintype "passive"))
    )
    (net (code "64") (name "/M-G9{slash}TIOA9{slash}AD1") (class "Default")
      (node (ref "H8") (pin "13") (pinfunction "13_13") (pintype "passive"))
      (node (ref "U3") (pin "C2") (pinfunction "PE0_C2") (pintype "passive"))
      (node (ref "U3") (pin "G2") (pinfunction "PC13_G2") (pintype "passive"))
      (node (ref "U3") (pin "L5") (pinfunction "PA15_L5") (pintype "passive"))
    )
    (net (code "65") (name "/M-G10{slash}TIOB9{slash}AD2") (class "Default")
      (node (ref "H8") (pin "14") (pinfunction "14_14") (pintype "passive"))
      (node (ref "U3") (pin "A1") (pinfunction "PE1_A1") (pintype "passive"))
      (node (ref "U3") (pin "G1") (pinfunction "PC15_G1") (pintype "passive"))
    )
    (net (code "66") (name "/M-SW-CFG") (class "Default")
      (node (ref "S2") (pin "1") (pinfunction "1_1") (pintype "passive"))
      (node (ref "U3") (pin "L3") (pinfunction "PC3_L3") (pintype "passive"))
    )
    (net (code "67") (name "/M-SW-LOG") (class "Default")
      (node (ref "S3") (pin "1") (pinfunction "1_1") (pintype "passive"))
      (node (ref "U3") (pin "M4") (pinfunction "PC7_M4") (pintype "passive"))
    )
    (net (code "68") (name "/M-SWD.SWDCLK") (class "Default")
      (node (ref "H5") (pin "4") (pinfunction "4_4") (pintype "passive"))
      (node (ref "U3") (pin "F9") (pinfunction "PB7_F9") (pintype "passive"))
    )
    (net (code "69") (name "/M-SWD.SWDIO") (class "Default")
      (node (ref "H5") (pin "2") (pinfunction "2_2") (pintype "passive"))
      (node (ref "U3") (pin "J11") (pinfunction "PB6_J11") (pintype "passive"))
    )
    (net (code "70") (name "/M-SWD.SWO") (class "Default")
      (node (ref "H5") (pin "6") (pinfunction "6_6") (pintype "passive"))
      (node (ref "U3") (pin "C10") (pinfunction "PB5_C10") (pintype "passive"))
    )
    (net (code "71") (name "/M-USB.D_N") (class "Default")
      (node (ref "U3") (pin "B4") (pinfunction "HSDM_B4") (pintype "passive"))
    )
    (net (code "72") (name "/M-USB.D_P") (class "Default")
      (node (ref "U3") (pin "A4") (pinfunction "HSDP_A4") (pintype "passive"))
    )
    (net (code "73") (name "/M-USB.ID") (class "Default")
      (node (ref "U3") (pin "J1") (pinfunction "PA17_J1") (pintype "passive"))
    )
    (net (code "75") (name "/M-~{RESET}") (class "Default")
      (node (ref "C34") (pin "1") (pinfunction "1_1") (pintype "passive"))
      (node (ref "D7") (pin "C") (pinfunction "C_C") (pintype "passive"))
      (node (ref "H5") (pin "10") (pinfunction "10_10") (pintype "passive"))
      (node (ref "R9") (pin "1") (pinfunction "1_1") (pintype "passive"))
      (node (ref "S1") (pin "2") (pinfunction "2_2") (pintype "passive"))
      (node (ref "U3") (pin "H12") (pinfunction "RESET_H12") (pintype "passive"))
    )
    (net (code "76") (name "/RS232.RxD") (class "Default")
      (node (ref "U3") (pin "K10") (pinfunction "PD28_K10") (pintype "passive"))
    )
    (net (code "77") (name "/RS232.TxD") (class "Default")
      (node (ref "U3") (pin "M1") (pinfunction "PD30_M1") (pintype "passive"))
    )
    (net (code "79") (name "/SD.CLK") (class "Default")
      (node (ref "U3") (pin "K8") (pinfunction "PA25_K8") (pintype "passive"))
    )
    (net (code "80") (name "/SD.CMD") (class "Default")
      (node (ref "U3") (pin "C9") (pinfunction "PA28_C9") (pintype "passive"))
    )
    (net (code "81") (name "/SD.D0") (class "Default")
      (node (ref "U3") (pin "A10") (pinfunction "PA30_A10") (pintype "passive"))
    )
    (net (code "82") (name "/SD.D1") (class "Default")
      (node (ref "U3") (pin "C8") (pinfunction "PA31_C8") (pintype "passive"))
    )
    (net (code "83") (name "/SD.D2") (class "Default")
      (node (ref "U3") (pin "J8") (pinfunction "PA26_J8") (pintype "passive"))
    )
    (net (code "84") (name "/SD.D3") (class "Default")
      (node (ref "U3") (pin "J10") (pinfunction "PA27_J10") (pintype "passive"))
    )
    (net (code "85") (name "/SD.DETECT") (class "Default")
      (node (ref "U3") (pin "D11") (pinfunction "PC16_D11") (pintype "passive"))
    )
    (net (code "87") (name "/SP330-DUPLEX") (class "Default")
      (node (ref "U3") (pin "B10") (pinfunction "PC18_B10") (pintype "passive"))
    )
    (net (code "88") (name "/SP330-SHDN") (class "Default")
      (node (ref "U3") (pin "H1") (pinfunction "PA19_H1") (pintype "passive"))
    )
    (net (code "89") (name "/SP330-SLEW") (class "Default")
      (node (ref "U3") (pin "H2") (pinfunction "PA18_H2") (pintype "passive"))
    )
    (net (code "90") (name "/VBG") (class "Default")
      (node (ref "C4") (pin "1") (pinfunction "1_1") (pintype "passive"))
      (node (ref "R4") (pin "1") (pinfunction "1_1") (pintype "passive"))
      (node (ref "U3") (pin "C4") (pinfunction "VBG_C4") (pintype "passive"))
    )
    (net (code "91") (name "/VDDPLL") (class "Default")
      (node (ref "C44") (pin "1") (pinfunction "1_1") (pintype "passive"))
      (node (ref "I6") (pin "1") (pinfunction "1_1") (pintype "passive"))
      (node (ref "U3") (pin "J7") (pinfunction "VDDPLL_J7") (pintype "passive"))
    )
    (net (code "92") (name "/VDDPLLUSB") (class "Default")
      (node (ref "C35") (pin "1") (pinfunction "1_1") (pintype "passive"))
      (node (ref "I5") (pin "1") (pinfunction "1_1") (pintype "passive"))
      (node (ref "U3") (pin "F8") (pinfunction "VDDPLLUSB_F8") (pintype "passive"))
    )
    (net (code "93") (name "/VDDUTMIC") (class "Default")
      (node (ref "C49") (pin "1") (pinfunction "1_1") (pintype "passive"))
      (node (ref "I7") (pin "1") (pinfunction "1_1") (pintype "passive"))
      (node (ref "U3") (pin "B3") (pinfunction "VDDUTMIC_B3") (pintype "passive"))
    )
    (net (code "94") (name "/VREFP") (class "Default")
      (node (ref "C8") (pin "1") (pinfunction "1_1") (pintype "passive"))
      (node (ref "I2") (pin "1") (pinfunction "1_1") (pintype "passive"))
      (node (ref "U3") (pin "D1") (pinfunction "VREFP_D1") (pintype "passive"))
    )
    (net (code "95") (name "/WINC-LED.Rx") (class "Default")
      (node (ref "R28") (pin "2") (pinfunction "2_2") (pintype "passive"))
      (node (ref "U3") (pin "B12") (pinfunction "PC17_B12") (pintype "passive"))
    )
    (net (code "96") (name "/WINC-LED.Tx") (class "Default")
      (node (ref "R29") (pin "2") (pinfunction "2_2") (pintype "passive"))
      (node (ref "U3") (pin "C12") (pinfunction "PD10_C12") (pintype "passive"))
    )
    (net (code "97") (name "/WINC.Grn") (class "Default")
      (node (ref "D5") (pin "4") (pinfunction "4_4") (pintype "passive"))
      (node (ref "R28") (pin "1") (pinfunction "1_1") (pintype "passive"))
    )
    (net (code "98") (name "/WINC.Red") (class "Default")
      (node (ref "D5") (pin "2") (pinfunction "2_2") (pintype "passive"))
      (node (ref "R29") (pin "1") (pinfunction "1_1") (pintype "passive"))
    )
    (net (code "99") (name "/WiFi-EN") (class "Default")
      (node (ref "U3") (pin "C7") (pinfunction "PC22_C7") (pintype "passive"))
    )
    (net (code "100") (name "/WiFi-IRQN") (class "Default")
      (node (ref "U3") (pin "C6") (pinfunction "PC23_C6") (pintype "passive"))
    )
    (net (code "101") (name "/WiFi-RST") (class "Default")
      (node (ref "U3") (pin "A7") (pinfunction "PC21_A7") (pintype "passive"))
    )
    (net (code "102") (name "/WiFi-SPI.CS") (class "Default")
      (node (ref "U3") (pin "C5") (pinfunction "PC25_C5") (pintype "passive"))
    )
    (net (code "103") (name "/WiFi-SPI.MISO") (class "Default")
      (node (ref "U3") (pin "F2") (pinfunction "PC26_F2") (pintype "passive"))
    )
    (net (code "104") (name "/WiFi-SPI.MOSI") (class "Default")
      (node (ref "U3") (pin "E2") (pinfunction "PC27_E2") (pintype "passive"))
    )
    (net (code "105") (name "/WiFi-SPI.SCLK") (class "Default")
      (node (ref "U3") (pin "B6") (pinfunction "PC24_B6") (pintype "passive"))
    )
    (net (code "107") (name "/XBee-DTR") (class "Default")
      (node (ref "U3") (pin "B5") (pinfunction "PD1_B5") (pintype "passive"))
    )
    (net (code "108") (name "/XBee-RST") (class "Default")
      (node (ref "U3") (pin "A6") (pinfunction "PA29_A6") (pintype "passive"))
    )
    (net (code "109") (name "/XBee-Ser.CTS") (class "Default")
      (node (ref "U3") (pin "J3") (pinfunction "PB3_J3") (pintype "passive"))
    )
    (net (code "110") (name "/XBee-Ser.RTS") (class "Default")
      (node (ref "U3") (pin "J2") (pinfunction "PB2_J2") (pintype "passive"))
    )
    (net (code "111") (name "/XBee-Ser.RxD") (class "Default")
      (node (ref "U3") (pin "G3") (pinfunction "PB1_G3") (pintype "passive"))
    )
    (net (code "112") (name "/XBee-Ser.TxD") (class "Default")
      (node (ref "U3") (pin "H4") (pinfunction "PB0_H4") (pintype "passive"))
    )
    (net (code "114") (name "/XBee-Supply-En") (class "Default")
      (node (ref "U3") (pin "L11") (pinfunction "PD17_L11") (pintype "passive"))
    )
    (net (code "115") (name "/Xin") (class "Default")
      (node (ref "U3") (pin "A2") (pinfunction "PB9_A2") (pintype "passive"))
      (node (ref "Y2") (pin "3") (pinfunction "OUT_3") (pintype "output"))
    )
    (net (code "116") (name "/Xin32") (class "Default")
      (node (ref "C7") (pin "1") (pinfunction "1_1") (pintype "passive"))
      (node (ref "U3") (pin "L2") (pinfunction "PA7_L2") (pintype "passive"))
      (node (ref "Y1") (pin "2") (pinfunction "2_2") (pintype "passive"))
    )
    (net (code "117") (name "/Xout") (class "Default")
      (node (ref "U3") (pin "A3") (pinfunction "PB8_A3") (pintype "passive"))
    )
    (net (code "118") (name "/Xout32") (class "Default")
      (node (ref "C6") (pin "1") (pinfunction "1_1") (pintype "passive"))
      (node (ref "U3") (pin "M2") (pinfunction "PA8_M2") (pintype "passive"))
      (node (ref "Y1") (pin "1") (pinfunction "1_1") (pintype "passive"))
    )
    (net (code "119") (name "/uINS-Data-Rdy") (class "Default")
      (node (ref "U3") (pin "A5") (pinfunction "PD2_A5") (pintype "passive"))
    )
    (net (code "120") (name "/uINS-SPI-EN") (class "Default")
      (node (ref "U3") (pin "A9") (pinfunction "PC20_A9") (pintype "passive"))
    )
    (net (code "121") (name "/uINS-Ser0.RxD") (class "Default")
      (node (ref "U3") (pin "B9") (pinfunction "PA6_B9") (pintype "passive"))
    )
    (net (code "122") (name "/uINS-Ser0.TxD") (class "Default")
      (node (ref "U3") (pin "M11") (pinfunction "PA5_M11") (pintype "passive"))
    )
    (net (code "124") (name "/uINS-Ser1.CS") (class "Default")
      (node (ref "U3") (pin "G10") (pinfunction "PD12_G10") (pintype "passive"))
    )
    (net (code "125") (name "/uINS-Ser1.RxD{slash}MOSI") (class "Default")
      (node (ref "U3") (pin "H9") (pinfunction "PD21_H9") (pintype "passive"))
      (node (ref "U3") (pin "L9") (pinfunction "PA10_L9") (pintype "passive"))
    )
    (net (code "126") (name "/uINS-Ser1.SCLK") (class "Default")
      (node (ref "U3") (pin "M8") (pinfunction "PD22_M8") (pintype "passive"))
    )
    (net (code "127") (name "/uINS-Ser1.TxD{slash}MISO") (class "Default")
      (node (ref "U3") (pin "K9") (pinfunction "PD20_K9") (pintype "passive"))
      (node (ref "U3") (pin "M12") (pinfunction "PA9_M12") (pintype "passive"))
    )
    (net (code "129") (name "BEE.3V3") (class "Default")
      (node (ref "H4") (pin "4") (pinfunction "4_4") (pintype "passive"))
      (node (ref "H4") (pin "5") (pinfunction "5_5") (pintype "passive"))
      (node (ref "H4") (pin "6") (pinfunction "6_6") (pintype "passive"))
    )
    (net (code "130") (name "GND") (class "Default")
      (node (ref "C11") (pin "2") (pinfunction "2_2") (pintype "passive"))
      (node (ref "C13") (pin "1") (pinfunction "1_1") (pintype "passive"))
      (node (ref "C19") (pin "2") (pinfunction "2_2") (pintype "passive"))
      (node (ref "C26") (pin "1") (pinfunction "1_1") (pintype "passive"))
      (node (ref "C30") (pin "1") (pinfunction "1_1") (pintype "passive"))
      (node (ref "C34") (pin "2") (pinfunction "2_2") (pintype "passive"))
      (node (ref "C35") (pin "2") (pinfunction "2_2") (pintype "passive"))
      (node (ref "C36") (pin "2") (pinfunction "2_2") (pintype "passive"))
      (node (ref "C37") (pin "2") (pinfunction "2_2") (pintype "passive"))
      (node (ref "C38") (pin "2") (pinfunction "2_2") (pintype "passive"))
      (node (ref "C39") (pin "2") (pinfunction "2_2") (pintype "passive"))
      (node (ref "C4") (pin "2") (pinfunction "2_2") (pintype "passive"))
      (node (ref "C40") (pin "2") (pinfunction "2_2") (pintype "passive"))
      (node (ref "C42") (pin "2") (pinfunction "2_2") (pintype "passive"))
      (node (ref "C43") (pin "2") (pinfunction "2_2") (pintype "passive"))
      (node (ref "C44") (pin "2") (pinfunction "2_2") (pintype "passive"))
      (node (ref "C45") (pin "2") (pinfunction "2_2") (pintype "passive"))
      (node (ref "C46") (pin "2") (pinfunction "2_2") (pintype "passive"))
      (node (ref "C47") (pin "2") (pinfunction "2_2") (pintype "passive"))
      (node (ref "C48") (pin "2") (pinfunction "2_2") (pintype "passive"))
      (node (ref "C49") (pin "2") (pinfunction "2_2") (pintype "passive"))
      (node (ref "C5") (pin "1") (pinfunction "1_1") (pintype "passive"))
      (node (ref "C50") (pin "2") (pinfunction "2_2") (pintype "passive"))
      (node (ref "C53") (pin "2") (pinfunction "2_2") (pintype "passive"))
      (node (ref "C6") (pin "2") (pinfunction "2_2") (pintype "passive"))
      (node (ref "C7") (pin "2") (pinfunction "2_2") (pintype "passive"))
      (node (ref "C8") (pin "2") (pinfunction "2_2") (pintype "passive"))
      (node (ref "C9") (pin "1") (pinfunction "1_1") (pintype "passive"))
      (node (ref "H4") (pin "0") (pinfunction "0_0") (pintype "passive"))
      (node (ref "H4") (pin "1") (pinfunction "1_1") (pintype "passive"))
      (node (ref "H4") (pin "2") (pinfunction "2_2") (pintype "passive"))
      (node (ref "H4") (pin "3") (pinfunction "3_3") (pintype "passive"))
      (node (ref "H5") (pin "3") (pinfunction "3_3") (pintype "passive"))
      (node (ref "H5") (pin "5") (pinfunction "5_5") (pintype "passive"))
      (node (ref "H5") (pin "9") (pinfunction "9_9") (pintype "passive"))
      (node (ref "H8") (pin "0") (pinfunction "0_0") (pintype "passive"))
      (node (ref "H8") (pin "1") (pinfunction "1_1") (pintype "passive"))
      (node (ref "H8") (pin "2") (pinfunction "2_2") (pintype "passive"))
      (node (ref "R4") (pin "2") (pinfunction "2_2") (pintype "passive"))
      (node (ref "S1") (pin "1") (pinfunction "1_1") (pintype "passive"))
      (node (ref "S2") (pin "2") (pinfunction "2_2") (pintype "passive"))
      (node (ref "S3") (pin "2") (pinfunction "2_2") (pintype "passive"))
      (node (ref "U2") (pin "4") (pinfunction "GND_4") (pintype "power_in"))
      (node (ref "U3") (pin "D2") (pinfunction "VREFN_D2") (pintype "passive"))
      (node (ref "U3") (pin "D5") (pinfunction "GNDANA_D5") (pintype "passive"))
      (node (ref "U3") (pin "E4") (pinfunction "PC0_E4") (pintype "passive"))
      (node (ref "U3") (pin "E5") (pinfunction "GNDUTMI_E5") (pintype "passive"))
      (node (ref "U3") (pin "E6") (pinfunction "GNDPLLUSB_E6") (pintype "passive"))
      (node (ref "U3") (pin "F5") (pinfunction "GND_F5") (pintype "power_in"))
      (node (ref "U3") (pin "F6") (pinfunction "GND_F6") (pintype "power_in"))
      (node (ref "U3") (pin "F7") (pinfunction "GNDPLL_F7") (pintype "passive"))
      (node (ref "U3") (pin "G4") (pinfunction "GND_G4") (pintype "power_in"))
      (node (ref "U3") (pin "G5") (pinfunction "GND_G5") (pintype "power_in"))
      (node (ref "U3") (pin "G6") (pinfunction "GND_G6") (pintype "power_in"))
      (node (ref "U3") (pin "G7") (pinfunction "GND_G7") (pintype "power_in"))
      (node (ref "U3") (pin "J4") (pinfunction "PC1_J4") (pintype "passive"))
      (node (ref "Y2") (pin "2") (pinfunction "GND_2") (pintype "passive"))
    )
    (net (code "131") (name "Net-(D7-PadA)") (class "Default")
      (node (ref "D7") (pin "A") (pinfunction "A_A") (pintype "passive"))
      (node (ref "R54") (pin "2") (pinfunction "2_2") (pintype "passive"))
    )
    (net (code "132") (name "VDDOUT") (class "Default")
      (node (ref "C36") (pin "1") (pinfunction "1_1") (pintype "passive"))
      (node (ref "C37") (pin "1") (pinfunction "1_1") (pintype "passive"))
      (node (ref "C38") (pin "1") (pinfunction "1_1") (pintype "passive"))
      (node (ref "C40") (pin "1") (pinfunction "1_1") (pintype "passive"))
      (node (ref "C47") (pin "1") (pinfunction "1_1") (pintype "passive"))
      (node (ref "C48") (pin "1") (pinfunction "1_1") (pintype "passive"))
      (node (ref "C50") (pin "1") (pinfunction "1_1") (pintype "passive"))
      (node (ref "I6") (pin "2") (pinfunction "2_2") (pintype "passive"))
      (node (ref "I7") (pin "2") (pinfunction "2_2") (pintype "passive"))
      (node (ref "U3") (pin "C3") (pinfunction "VDDOUT_C3") (pintype "passive"))
      (node (ref "U3") (pin "E8") (pinfunction "VDDCORE_E8") (pintype "passive"))
      (node (ref "U3") (pin "H5") (pinfunction "VDDCORE_H5") (pintype "passive"))
      (node (ref "U3") (pin "H8") (pinfunction "VDDCORE_H8") (pintype "passive"))
    )
    (net (code "133") (name "unconnected-(D3-Pad3)") (class "Default")
      (node (ref "D3") (pin "3") (pinfunction "3_3") (pintype "passive"))
    )
    (net (code "134") (name "unconnected-(D4-Pad3)") (class "Default")
      (node (ref "D4") (pin "3") (pinfunction "3_3") (pintype "passive"))
    )
    (net (code "135") (name "unconnected-(D5-Pad3)") (class "Default")
      (node (ref "D5") (pin "3") (pinfunction "3_3") (pintype "passive"))
    )
    (net (code "136") (name "unconnected-(H5-Pad7)") (class "Default")
      (node (ref "H5") (pin "7") (pinfunction "7_7") (pintype "passive"))
    )
    (net (code "137") (name "unconnected-(H5-Pad8)") (class "Default")
      (node (ref "H5") (pin "8") (pinfunction "8_8") (pintype "passive"))
    )
    (net (code "138") (name "unconnected-(U3-JTAGSEL-PadB11)") (class "Default")
      (node (ref "U3") (pin "B11") (pinfunction "JTAGSEL_B11") (pintype "passive"))
    )
    (net (code "139") (name "unconnected-(U3-PA14-PadK6)") (class "Default")
      (node (ref "U3") (pin "K6") (pinfunction "PA14_K6") (pintype "passive"))
    )
    (net (code "140") (name "unconnected-(U3-PA22-PadK3)") (class "Default")
      (node (ref "U3") (pin "K3") (pinfunction "PA22_K3") (pintype "passive"))
    )
    (net (code "141") (name "unconnected-(U3-PC4-PadJ5)") (class "Default")
      (node (ref "U3") (pin "J5") (pinfunction "PC4_J5") (pintype "passive"))
    )
    (net (code "142") (name "unconnected-(U3-PC19-PadD8)") (class "Default")
      (node (ref "U3") (pin "D8") (pinfunction "PC19_D8") (pintype "passive"))
    )
    (net (code "143") (name "unconnected-(U3-PD5-PadD7)") (class "Default")
      (node (ref "U3") (pin "D7") (pinfunction "PD5_D7") (pintype "passive"))
    )
    (net (code "144") (name "unconnected-(U3-PD8-PadE9)") (class "Default")
      (node (ref "U3") (pin "E9") (pinfunction "PD8_E9") (pintype "passive"))
    )
    (net (code "145") (name "unconnected-(U3-PD9-PadD9)") (class "Default")
      (node (ref "U3") (pin "D9") (pinfunction "PD9_D9") (pintype "passive"))
    )
    (net (code "146") (name "unconnected-(U3-PD11-PadE11)") (class "Default")
      (node (ref "U3") (pin "E11") (pinfunction "PD11_E11") (pintype "passive"))
    )
    (net (code "147") (name "unconnected-(U3-PD13-PadG9)") (class "Default")
      (node (ref "U3") (pin "G9") (pinfunction "PD13_G9") (pintype "passive"))
    )
    (net (code "148") (name "unconnected-(U3-PD14-PadH10)") (class "Default")
      (node (ref "U3") (pin "H10") (pinfunction "PD14_H10") (pintype "passive"))
    )
    (net (code "149") (name "unconnected-(U3-PD24-PadM6)") (class "Default")
      (node (ref "U3") (pin "M6") (pinfunction "PD24_M6") (pintype "passive"))
    )
    (net (code "150") (name "unconnected-(U3-PD29-PadD10)") (class "Default")
      (node (ref "U3") (pin "D10") (pinfunction "PD29_D10") (pintype "passive"))
    )
    (net (code "151") (name "unconnected-(U3-PD31-PadD3)") (class "Default")
      (node (ref "U3") (pin "D3") (pinfunction "PD31_D3") (pintype "passive"))
    )
    (net (code "152") (name "unconnected-(U3-PE5-PadL1)") (class "Default")
      (node (ref "U3") (pin "L1") (pinfunction "PE5_L1") (pintype "passive"))
    )
    (net (code "153") (name "unconnected-(U3-TST-PadH11)") (class "Default")
      (node (ref "U3") (pin "H11") (pinfunction "TST_H11") (pintype "passive"))
    )
  )
)
